# Motor-X.net
KiCad netlist of a schematic drawn in Altium Designer
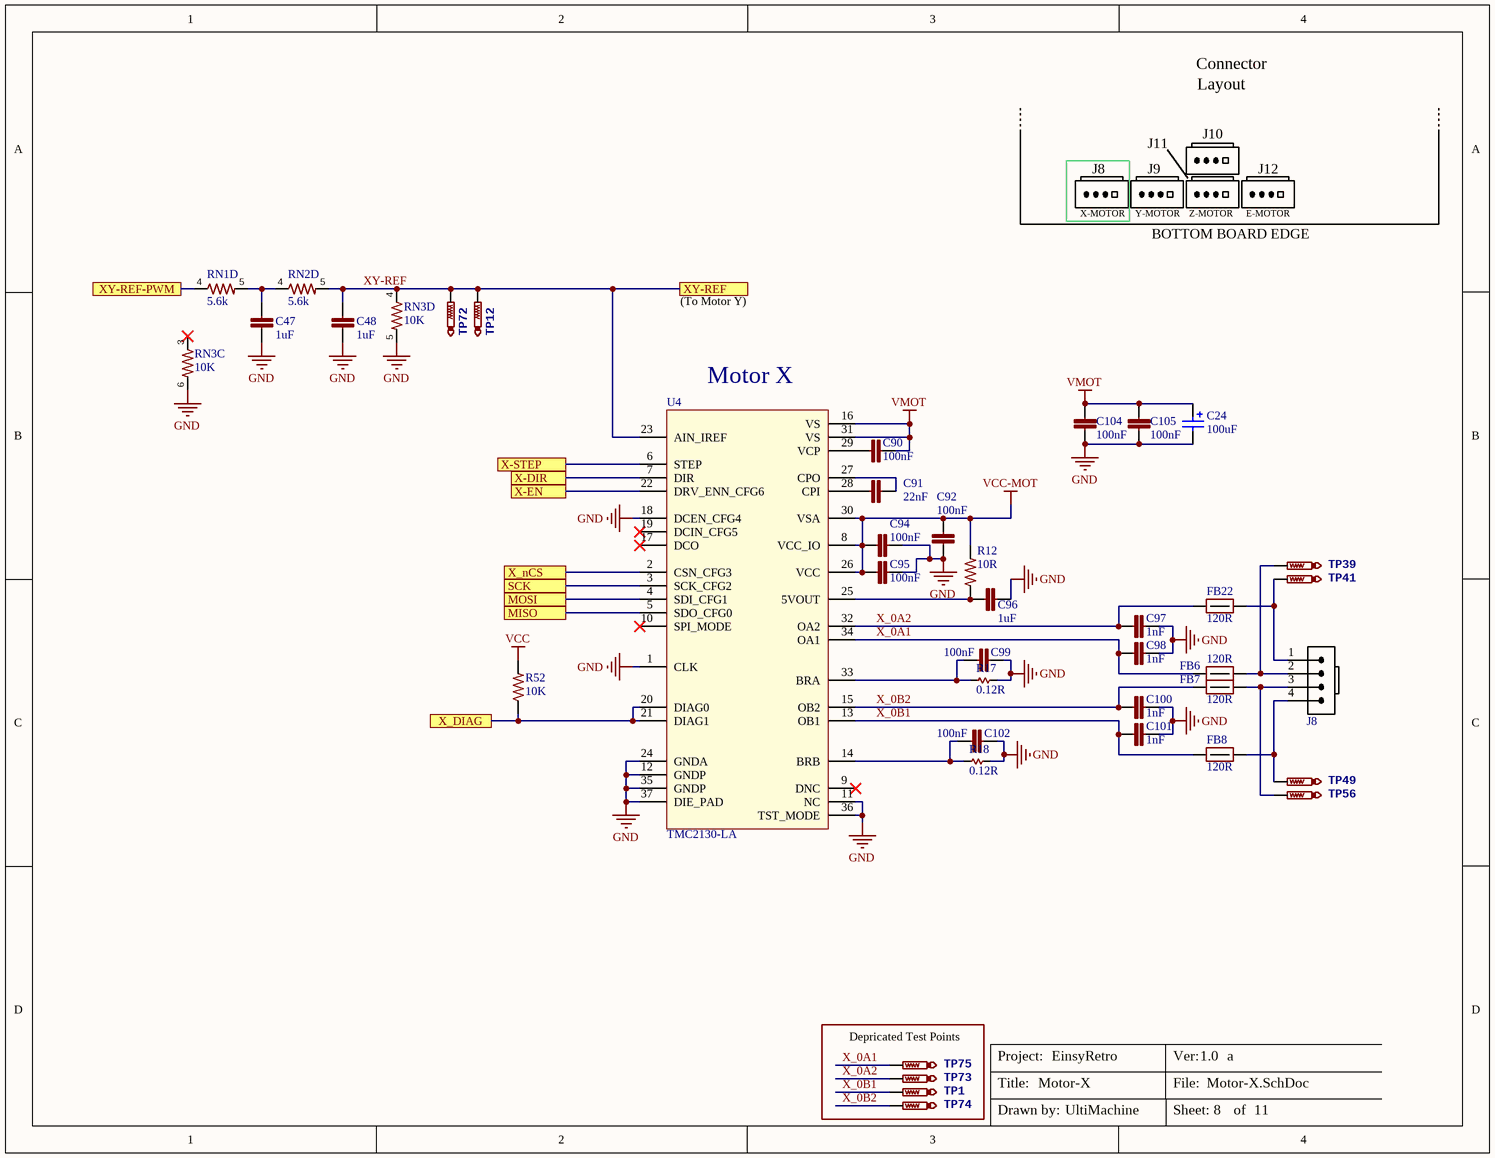
[diagram p0: Motor-X.SchDoc]

(export (version "E")
  (design (tool "Eeschema 10.0.6"))
  (components
    (comp (ref "C24")
      (value "100uF")
      (footprint "CAP-ELEC-063063077")
      (description "CAP ALUM 100UF 35V 20% SMD")
      (fields (field (name "MANUFACTURER") "Nichicon") (field (name "TOLERANCE") "+/- 20%"))
      (libsource (lib "3Delight") (part "UWT1V101MCL1GS"))
    )
    (comp (ref "C47")
      (value "1uF")
      (footprint "C0402")
      (description "CAP CER 0402 1uF 6.3V 10% X5R")
      (fields (field (name "MANUFACTURER") "Murata") (field (name "TOLERANCE") "+/- 10%"))
      (libsource (lib "") (part "GRM155R60J105KE19D_1"))
    )
    (comp (ref "C48")
      (value "1uF")
      (footprint "C0402")
      (description "CAP CER 0402 1uF 6.3V 10% X5R")
      (fields (field (name "MANUFACTURER") "Murata") (field (name "TOLERANCE") "+/- 10%"))
      (libsource (lib "") (part "GRM155R60J105KE19D_1"))
    )
    (comp (ref "C90")
      (value "100nF")
      (footprint "C0603")
      (description "CAP CER 0603 100nF 50V 10% X7R")
      (fields (field (name "MANUFACTURER") "Kemet") (field (name "TOLERANCE") "+/- 10%"))
      (libsource (lib "3Delight") (part "C0603C104K5RACTU"))
    )
    (comp (ref "C91")
      (value "22nF")
      (footprint "C0402")
      (description "CAP CER 0402 22nF ±10% 50V X7R")
      (fields (field (name "MANUFACTURER") "YAGEO") (field (name "TOLERANCE") "+/- 10%"))
      (libsource (lib "3Delight") (part "GCM155R71H223KA55D"))
    )
    (comp (ref "C92")
      (value "100nF")
      (footprint "C0402")
      (description "CAP CER 0402 100nF 16V 10% X7R")
      (fields (field (name "MANUFACTURER") "Murata") (field (name "TOLERANCE") "+/- 10%"))
      (libsource (lib "3Delight") (part "GRM155R71C104KA88D"))
    )
    (comp (ref "C94")
      (value "100nF")
      (footprint "C0402")
      (description "CAP CER 0402 100nF 16V 10% X7R")
      (fields (field (name "MANUFACTURER") "Murata") (field (name "TOLERANCE") "+/- 10%"))
      (libsource (lib "") (part "GRM155R71C104KA88D_1"))
    )
    (comp (ref "C95")
      (value "100nF")
      (footprint "C0402")
      (description "CAP CER 0402 100nF 16V 10% X7R")
      (fields (field (name "MANUFACTURER") "Murata") (field (name "TOLERANCE") "+/- 10%"))
      (libsource (lib "") (part "GRM155R71C104KA88D_1"))
    )
    (comp (ref "C96")
      (value "1uF")
      (footprint "C0402")
      (description "CAP CER 0402 1uF 6.3V 10% X5R")
      (fields (field (name "MANUFACTURER") "Murata") (field (name "TOLERANCE") "+/- 10%"))
      (libsource (lib "3Delight") (part "GRM155R60J105KE19D"))
    )
    (comp (ref "C97")
      (value "1nF")
      (footprint "C0603")
      (description "CAP CER 0603  1nF 50v 10% X7R")
      (fields (field (name "MANUFACTURER") "Kemet") (field (name "TOLERANCE") "+/- 10%"))
      (libsource (lib "3Delight") (part "C0603C102K5RACTU"))
    )
    (comp (ref "C98")
      (value "1nF")
      (footprint "C0603")
      (description "CAP CER 0603  1nF 50v 10% X7R")
      (fields (field (name "MANUFACTURER") "Kemet") (field (name "TOLERANCE") "+/- 10%"))
      (libsource (lib "3Delight") (part "C0603C102K5RACTU"))
    )
    (comp (ref "C99")
      (value "100nF")
      (footprint "C0603")
      (description "CAP CER 0603 100nF 50V 10% X7R")
      (fields (field (name "MANUFACTURER") "Kemet") (field (name "TOLERANCE") "+/- 10%"))
      (libsource (lib "") (part "C0603C104K5RACTU_1"))
    )
    (comp (ref "C100")
      (value "1nF")
      (footprint "C0603")
      (description "CAP CER 0603  1nF 50v 10% X7R")
      (fields (field (name "MANUFACTURER") "Kemet") (field (name "TOLERANCE") "+/- 10%"))
      (libsource (lib "3Delight") (part "C0603C102K5RACTU"))
    )
    (comp (ref "C101")
      (value "1nF")
      (footprint "C0603")
      (description "CAP CER 0603  1nF 50v 10% X7R")
      (fields (field (name "MANUFACTURER") "Kemet") (field (name "TOLERANCE") "+/- 10%"))
      (libsource (lib "3Delight") (part "C0603C102K5RACTU"))
    )
    (comp (ref "C102")
      (value "100nF")
      (footprint "C0603")
      (description "CAP CER 0603 100nF 50V 10% X7R")
      (fields (field (name "MANUFACTURER") "Kemet") (field (name "TOLERANCE") "+/- 10%"))
      (libsource (lib "") (part "C0603C104K5RACTU_1"))
    )
    (comp (ref "C104")
      (value "100nF")
      (footprint "C0603")
      (description "CAP CER 0603 100nF 50V 10% X7R")
      (fields (field (name "MANUFACTURER") "Kemet") (field (name "TOLERANCE") "+/- 10%"))
      (libsource (lib "") (part "C0603C104K5RACTU_2"))
    )
    (comp (ref "C105")
      (value "100nF")
      (footprint "C0603")
      (description "CAP CER 0603 100nF 50V 10% X7R")
      (fields (field (name "MANUFACTURER") "Kemet") (field (name "TOLERANCE") "+/- 10%"))
      (libsource (lib "") (part "C0603C104K5RACTU_2"))
    )
    (comp (ref "FB6")
      (value "120R")
      (footprint "FB0603")
      (description "FERRITE BEAD 120 OHM 0603 1LN")
      (fields (field (name "MANUFACTURER") "Samsung") (field (name "PART") "FERRITE 120R 3A 0603"))
      (libsource (lib "Inductors") (part "FERRITE 120R 3A 0603"))
    )
    (comp (ref "FB7")
      (value "120R")
      (footprint "FB0603")
      (description "FERRITE BEAD 120 OHM 0603 1LN")
      (fields (field (name "MANUFACTURER") "Samsung") (field (name "PART") "FERRITE 120R 3A 0603"))
      (libsource (lib "Inductors") (part "FERRITE 120R 3A 0603"))
    )
    (comp (ref "FB8")
      (value "120R")
      (footprint "FB0603")
      (description "FERRITE BEAD 120 OHM 0603 1LN")
      (fields (field (name "MANUFACTURER") "Samsung") (field (name "PART") "FERRITE 120R 3A 0603"))
      (libsource (lib "Inductors") (part "FERRITE 120R 3A 0603"))
    )
    (comp (ref "FB22")
      (value "120R")
      (footprint "FB0603")
      (description "FERRITE BEAD 120 OHM 0603 1LN")
      (fields (field (name "MANUFACTURER") "Samsung") (field (name "PART") "FERRITE 120R 3A 0603"))
      (libsource (lib "Inductors") (part "FERRITE 120R 3A 0603"))
    )
    (comp (ref "J8")
      (value "Molex 0705430003")
      (footprint "4POL254 PIN-IN-PASTE")
      (description "Molex 4 Pin Clip Connector - Pin In Paste footprint")
      (libsource (lib "Connectors") (part "Molex 0705430003 PIP"))
    )
    (comp (ref "R12")
      (value "10R")
      (footprint "R0402")
      (description "RES SMD 10 OHM 1% 1/16W 0402")
      (fields (field (name "MANUFACTURER") "Yageo") (field (name "TOLERANCE") "+/- 1%"))
      (libsource (lib "3Delight") (part "RC0402FR-0710RL"))
    )
    (comp (ref "R17")
      (value "0.12R")
      (footprint "R1206")
      (description "RES 0.12 OHM 1% 1/2W 1206")
      (fields (field (name "TOLERANCE") "+/- 1%"))
      (libsource (lib "Resistors") (part "0.12R 1% 1206"))
    )
    (comp (ref "R18")
      (value "0.12R")
      (footprint "R1206")
      (description "RES 0.12 OHM 1% 1/2W 1206")
      (fields (field (name "TOLERANCE") "+/- 1%"))
      (libsource (lib "Resistors") (part "0.12R 1% 1206"))
    )
    (comp (ref "R52")
      (value "10K")
      (footprint "R0402")
      (description "RES SMD 10K OHM 1% 1/16W 0402")
      (fields (field (name "MANUFACTURER") "Yageo") (field (name "PART") "10k 1% 0402"))
      (libsource (lib "3Delight") (part "RC0402FR-0710KP"))
    )
    (comp (ref "RN1")
      (value "5.6k")
      (footprint "CAY16")
      (description "RES ARRAY 4 RES 5.6K OHM 1206")
      (fields (field (name "MANUFACTURER") "Bourns") (field (name "TOLERANCE") "+/- 5%"))
      (libsource (lib "Resistors") (part "5.6k x 4 5% 1206"))
    )
    (comp (ref "RN2")
      (value "5.6k")
      (footprint "CAY16")
      (description "RES ARRAY 4 RES 5.6K OHM 1206")
      (fields (field (name "MANUFACTURER") "Bourns") (field (name "TOLERANCE") "+/- 5%"))
      (libsource (lib "Resistors") (part "5.6k x 4 5% 1206"))
    )
    (comp (ref "RN3")
      (value "10K")
      (footprint "CAY16")
      (description "RES ARRAY 4 RES 10K 1206 62.5mW 5%")
      (fields (field (name "MANUFACTURER") "Bourns") (field (name "TOLERANCE") "+/- 5%"))
      (libsource (lib "3Delight") (part "CAY16-103J4LF"))
    )
    (comp (ref "TP1")
      (value "TestPoint")
      (footprint "TP1-27")
      (description "Test Point")
      (libsource (lib "3Delight") (part "TestPoint"))
    )
    (comp (ref "TP12")
      (value "TestPoint")
      (footprint "TP1-27")
      (description "Test Point")
      (libsource (lib "") (part "TestPoint_1"))
    )
    (comp (ref "TP39")
      (value "TestPoint")
      (footprint "TP1-27")
      (description "Test Point")
      (libsource (lib "3Delight") (part "TestPoint"))
    )
    (comp (ref "TP41")
      (value "TestPoint")
      (footprint "TP1-27")
      (description "Test Point")
      (libsource (lib "3Delight") (part "TestPoint"))
    )
    (comp (ref "TP49")
      (value "TestPoint")
      (footprint "TP1-27")
      (description "Test Point")
      (libsource (lib "3Delight") (part "TestPoint"))
    )
    (comp (ref "TP56")
      (value "TestPoint")
      (footprint "TP1-27")
      (description "Test Point")
      (libsource (lib "3Delight") (part "TestPoint"))
    )
    (comp (ref "TP72")
      (value "TestPoint")
      (footprint "TP1-27")
      (description "Test Point")
      (libsource (lib "") (part "TestPoint_1"))
    )
    (comp (ref "TP73")
      (value "TestPoint")
      (footprint "TP1-27")
      (description "Test Point")
      (libsource (lib "3Delight") (part "TestPoint"))
    )
    (comp (ref "TP74")
      (value "TestPoint")
      (footprint "TP1-27")
      (description "Test Point")
      (libsource (lib "3Delight") (part "TestPoint"))
    )
    (comp (ref "TP75")
      (value "TestPoint")
      (footprint "TP1-27")
      (description "Test Point")
      (libsource (lib "3Delight") (part "TestPoint"))
    )
    (comp (ref "U4")
      (value "TMC2130-LA")
      (footprint "QFN36-50P500X600X900_HS-37N")
      (description "IC STEPPER MOTOR DVR SPI 36QFN")
      (fields (field (name "MANUFACTURER") "Trinamic") (field (name "PART") "TMC2130"))
      (libsource (lib "3Delight") (part "TMC2130-LA-T"))
    )
  )
  (nets
    (net (code "1") (name "/MISO") (class "Default")
      (node (ref "U4") (pin "5") (pinfunction "SDO_CFG0_5") (pintype "passive"))
    )
    (net (code "2") (name "/MOSI") (class "Default")
      (node (ref "U4") (pin "4") (pinfunction "SDI_CFG1_4") (pintype "passive"))
    )
    (net (code "3") (name "/SCK") (class "Default")
      (node (ref "U4") (pin "3") (pinfunction "SCK_CFG2_3") (pintype "passive"))
    )
    (net (code "4") (name "/X-DIR") (class "Default")
      (node (ref "U4") (pin "7") (pinfunction "DIR_7") (pintype "passive"))
    )
    (net (code "5") (name "/X-EN") (class "Default")
      (node (ref "U4") (pin "22") (pinfunction "DRV_ENN_CFG6_22") (pintype "passive"))
    )
    (net (code "6") (name "/X-STEP") (class "Default")
      (node (ref "U4") (pin "6") (pinfunction "STEP_6") (pintype "passive"))
    )
    (net (code "7") (name "/XY-REF") (class "Default")
      (node (ref "C48") (pin "1") (pinfunction "1_1") (pintype "passive"))
      (node (ref "RN2") (pin "5") (pinfunction "2_5") (pintype "passive"))
      (node (ref "RN3") (pin "4") (pinfunction "1_4") (pintype "passive"))
      (node (ref "TP12") (pin "TP") (pinfunction "TP_TP") (pintype "passive"))
      (node (ref "TP72") (pin "TP") (pinfunction "TP_TP") (pintype "passive"))
      (node (ref "U4") (pin "23") (pinfunction "AIN_IREF_23") (pintype "passive"))
    )
    (net (code "8") (name "/XY-REF-PWM") (class "Default")
      (node (ref "RN1") (pin "4") (pinfunction "1_4") (pintype "passive"))
    )
    (net (code "9") (name "/X_0A1") (class "Default")
      (node (ref "C98") (pin "1") (pinfunction "1_1") (pintype "passive"))
      (node (ref "FB6") (pin "1") (pinfunction "1_1") (pintype "passive"))
      (node (ref "TP75") (pin "TP") (pinfunction "TP_TP") (pintype "passive"))
      (node (ref "U4") (pin "34") (pinfunction "OA1_34") (pintype "passive"))
    )
    (net (code "10") (name "/X_0A2") (class "Default")
      (node (ref "C97") (pin "1") (pinfunction "1_1") (pintype "passive"))
      (node (ref "FB22") (pin "1") (pinfunction "1_1") (pintype "passive"))
      (node (ref "TP73") (pin "TP") (pinfunction "TP_TP") (pintype "passive"))
      (node (ref "U4") (pin "32") (pinfunction "OA2_32") (pintype "passive"))
    )
    (net (code "11") (name "/X_0B1") (class "Default")
      (node (ref "C101") (pin "1") (pinfunction "1_1") (pintype "passive"))
      (node (ref "FB8") (pin "1") (pinfunction "1_1") (pintype "passive"))
      (node (ref "TP1") (pin "TP") (pinfunction "TP_TP") (pintype "passive"))
      (node (ref "U4") (pin "13") (pinfunction "OB1_13") (pintype "passive"))
    )
    (net (code "12") (name "/X_0B2") (class "Default")
      (node (ref "C100") (pin "1") (pinfunction "1_1") (pintype "passive"))
      (node (ref "FB7") (pin "1") (pinfunction "1_1") (pintype "passive"))
      (node (ref "TP74") (pin "TP") (pinfunction "TP_TP") (pintype "passive"))
      (node (ref "U4") (pin "15") (pinfunction "OB2_15") (pintype "passive"))
    )
    (net (code "13") (name "/X_DIAG") (class "Default")
      (node (ref "R52") (pin "1") (pinfunction "1_1") (pintype "passive"))
      (node (ref "U4") (pin "20") (pinfunction "DIAG0_20") (pintype "passive"))
      (node (ref "U4") (pin "21") (pinfunction "DIAG1_21") (pintype "passive"))
    )
    (net (code "14") (name "/X_nCS") (class "Default")
      (node (ref "U4") (pin "2") (pinfunction "CSN_CFG3_2") (pintype "passive"))
    )
    (net (code "15") (name "GND") (class "Default")
      (node (ref "C100") (pin "2") (pinfunction "2_2") (pintype "passive"))
      (node (ref "C101") (pin "2") (pinfunction "2_2") (pintype "passive"))
      (node (ref "C102") (pin "1") (pinfunction "1_1") (pintype "passive"))
      (node (ref "C104") (pin "1") (pinfunction "1_1") (pintype "passive"))
      (node (ref "C105") (pin "1") (pinfunction "1_1") (pintype "passive"))
      (node (ref "C24") (pin "2") (pinfunction "2_2") (pintype "passive"))
      (node (ref "C47") (pin "2") (pinfunction "2_2") (pintype "passive"))
      (node (ref "C48") (pin "2") (pinfunction "2_2") (pintype "passive"))
      (node (ref "C92") (pin "1") (pinfunction "1_1") (pintype "passive"))
      (node (ref "C94") (pin "1") (pinfunction "1_1") (pintype "passive"))
      (node (ref "C95") (pin "1") (pinfunction "1_1") (pintype "passive"))
      (node (ref "C96") (pin "2") (pinfunction "2_2") (pintype "passive"))
      (node (ref "C97") (pin "2") (pinfunction "2_2") (pintype "passive"))
      (node (ref "C98") (pin "2") (pinfunction "2_2") (pintype "passive"))
      (node (ref "C99") (pin "1") (pinfunction "1_1") (pintype "passive"))
      (node (ref "R17") (pin "2") (pinfunction "2_2") (pintype "passive"))
      (node (ref "R18") (pin "2") (pinfunction "2_2") (pintype "passive"))
      (node (ref "RN3") (pin "5") (pinfunction "2_5") (pintype "passive"))
      (node (ref "RN3") (pin "6") (pinfunction "2_6") (pintype "passive"))
      (node (ref "U4") (pin "1") (pinfunction "CLK_1") (pintype "passive"))
      (node (ref "U4") (pin "11") (pinfunction "NC_11") (pintype "passive"))
      (node (ref "U4") (pin "12") (pinfunction "GNDP_12") (pintype "passive"))
      (node (ref "U4") (pin "18") (pinfunction "DCEN_CFG4_18") (pintype "passive"))
      (node (ref "U4") (pin "24") (pinfunction "GNDA_24") (pintype "passive"))
      (node (ref "U4") (pin "35") (pinfunction "GNDP_35") (pintype "passive"))
      (node (ref "U4") (pin "36") (pinfunction "TST_MODE_36") (pintype "passive"))
      (node (ref "U4") (pin "37") (pinfunction "DIE_PAD_37") (pintype "passive"))
    )
    (net (code "16") (name "Net-(FB6-Pad2)") (class "Default")
      (node (ref "FB6") (pin "2") (pinfunction "2_2") (pintype "passive"))
      (node (ref "J8") (pin "2") (pinfunction "2_2") (pintype "passive"))
      (node (ref "TP39") (pin "TP") (pinfunction "TP_TP") (pintype "passive"))
    )
    (net (code "17") (name "Net-(FB7-Pad2)") (class "Default")
      (node (ref "FB7") (pin "2") (pinfunction "2_2") (pintype "passive"))
      (node (ref "J8") (pin "3") (pinfunction "3_3") (pintype "passive"))
      (node (ref "TP56") (pin "TP") (pinfunction "TP_TP") (pintype "passive"))
    )
    (net (code "18") (name "Net-(FB8-Pad2)") (class "Default")
      (node (ref "FB8") (pin "2") (pinfunction "2_2") (pintype "passive"))
      (node (ref "J8") (pin "4") (pinfunction "4_4") (pintype "passive"))
      (node (ref "TP49") (pin "TP") (pinfunction "TP_TP") (pintype "passive"))
    )
    (net (code "19") (name "Net-(FB22-Pad2)") (class "Default")
      (node (ref "FB22") (pin "2") (pinfunction "2_2") (pintype "passive"))
      (node (ref "J8") (pin "1") (pinfunction "1_1") (pintype "passive"))
      (node (ref "TP41") (pin "TP") (pinfunction "TP_TP") (pintype "passive"))
    )
    (net (code "20") (name "Net-(RN1D-2)") (class "Default")
      (node (ref "C47") (pin "1") (pinfunction "1_1") (pintype "passive"))
      (node (ref "RN1") (pin "5") (pinfunction "2_5") (pintype "passive"))
      (node (ref "RN2") (pin "4") (pinfunction "1_4") (pintype "passive"))
    )
    (net (code "21") (name "Net-(U4-5VOUT)") (class "Default")
      (node (ref "C96") (pin "1") (pinfunction "1_1") (pintype "passive"))
      (node (ref "R12") (pin "1") (pinfunction "1_1") (pintype "passive"))
      (node (ref "U4") (pin "25") (pinfunction "5VOUT_25") (pintype "passive"))
    )
    (net (code "22") (name "Net-(U4-BRA)") (class "Default")
      (node (ref "C99") (pin "2") (pinfunction "2_2") (pintype "passive"))
      (node (ref "R17") (pin "1") (pinfunction "1_1") (pintype "passive"))
      (node (ref "U4") (pin "33") (pinfunction "BRA_33") (pintype "passive"))
    )
    (net (code "23") (name "Net-(U4-BRB)") (class "Default")
      (node (ref "C102") (pin "2") (pinfunction "2_2") (pintype "passive"))
      (node (ref "R18") (pin "1") (pinfunction "1_1") (pintype "passive"))
      (node (ref "U4") (pin "14") (pinfunction "BRB_14") (pintype "passive"))
    )
    (net (code "24") (name "Net-(U4-CPI)") (class "Default")
      (node (ref "C91") (pin "1") (pinfunction "1_1") (pintype "passive"))
      (node (ref "U4") (pin "28") (pinfunction "CPI_28") (pintype "passive"))
    )
    (net (code "25") (name "Net-(U4-CPO)") (class "Default")
      (node (ref "C91") (pin "2") (pinfunction "2_2") (pintype "passive"))
      (node (ref "U4") (pin "27") (pinfunction "CPO_27") (pintype "passive"))
    )
    (net (code "26") (name "Net-(U4-VCP)") (class "Default")
      (node (ref "C90") (pin "1") (pinfunction "1_1") (pintype "passive"))
      (node (ref "U4") (pin "29") (pinfunction "VCP_29") (pintype "passive"))
    )
    (net (code "27") (name "VCC") (class "Default")
      (node (ref "R52") (pin "2") (pinfunction "2_2") (pintype "passive"))
    )
    (net (code "28") (name "VCC-MOT") (class "Default")
      (node (ref "C92") (pin "2") (pinfunction "2_2") (pintype "passive"))
      (node (ref "C94") (pin "2") (pinfunction "2_2") (pintype "passive"))
      (node (ref "C95") (pin "2") (pinfunction "2_2") (pintype "passive"))
      (node (ref "R12") (pin "2") (pinfunction "2_2") (pintype "passive"))
      (node (ref "U4") (pin "26") (pinfunction "VCC_26") (pintype "passive"))
      (node (ref "U4") (pin "30") (pinfunction "VSA_30") (pintype "passive"))
      (node (ref "U4") (pin "8") (pinfunction "VCC_IO_8") (pintype "passive"))
    )
    (net (code "29") (name "VMOT") (class "Default")
      (node (ref "C104") (pin "2") (pinfunction "2_2") (pintype "passive"))
      (node (ref "C105") (pin "2") (pinfunction "2_2") (pintype "passive"))
      (node (ref "C24") (pin "1") (pinfunction "1_1") (pintype "passive"))
      (node (ref "C90") (pin "2") (pinfunction "2_2") (pintype "passive"))
      (node (ref "U4") (pin "16") (pinfunction "VS_16") (pintype "passive"))
      (node (ref "U4") (pin "31") (pinfunction "VS_31") (pintype "passive"))
    )
    (net (code "30") (name "unconnected-(RN3C-1-Pad3)") (class "Default")
      (node (ref "RN3") (pin "3") (pinfunction "1_3") (pintype "passive+no_connect"))
    )
    (net (code "31") (name "unconnected-(U4-DCIN_CFG5-Pad19)") (class "Default")
      (node (ref "U4") (pin "19") (pinfunction "DCIN_CFG5_19") (pintype "passive+no_connect"))
    )
    (net (code "32") (name "unconnected-(U4-DCO-Pad17)") (class "Default")
      (node (ref "U4") (pin "17") (pinfunction "DCO_17") (pintype "passive+no_connect"))
    )
    (net (code "33") (name "unconnected-(U4-DNC-Pad9)") (class "Default")
      (node (ref "U4") (pin "9") (pinfunction "DNC_9") (pintype "passive+no_connect"))
    )
    (net (code "34") (name "unconnected-(U4-SPI_MODE-Pad10)") (class "Default")
      (node (ref "U4") (pin "10") (pinfunction "SPI_MODE_10") (pintype "passive+no_connect"))
    )
  )
)
